# eCore_USB.net
KiCad netlist of a schematic drawn in Altium Designer
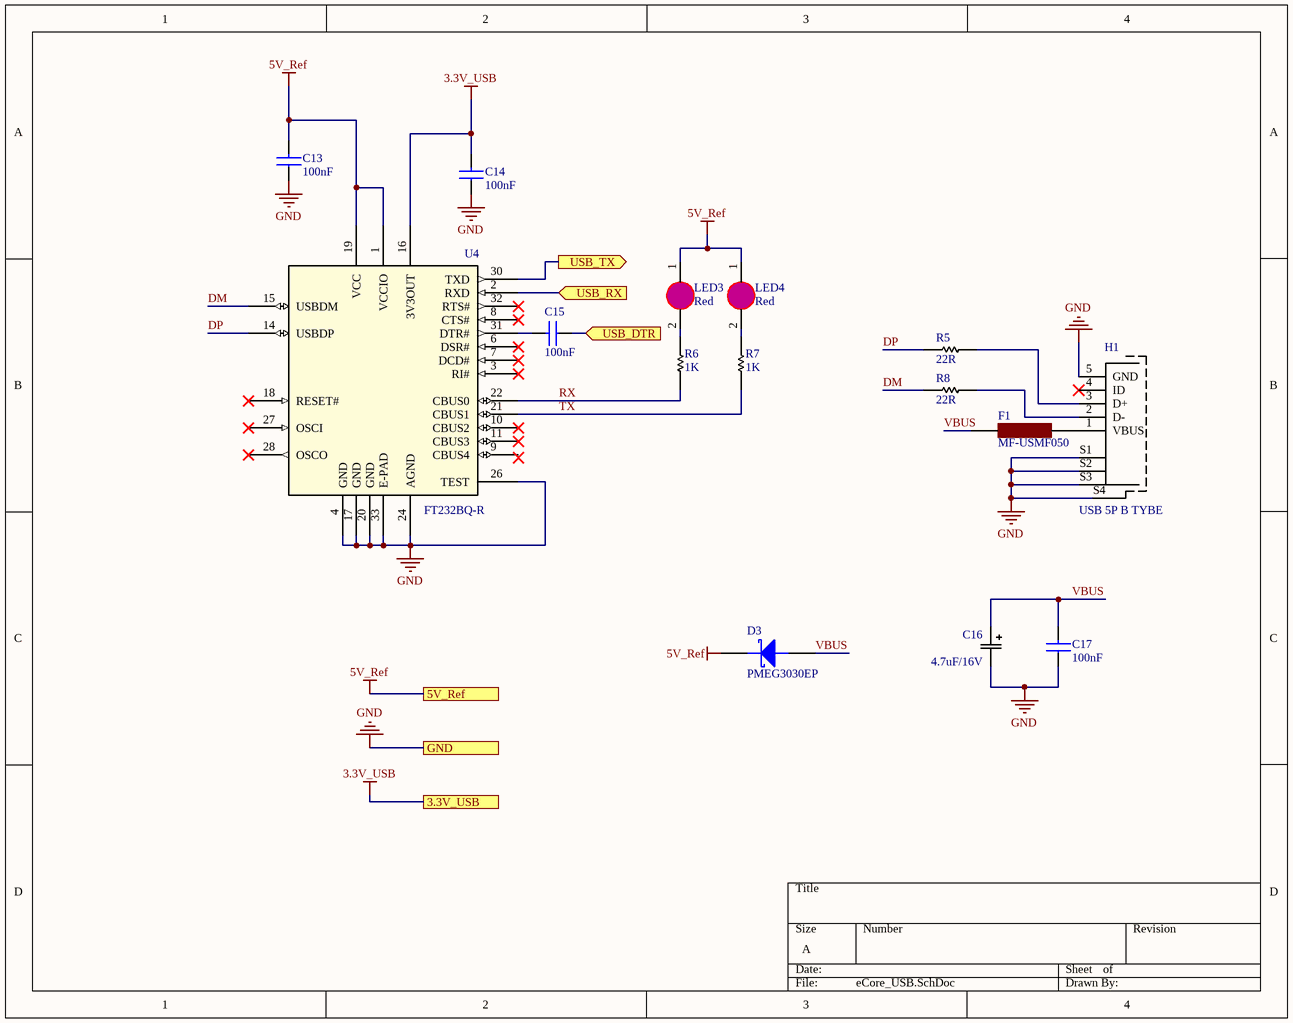
[diagram p0: eCore_USB.SchDoc]

(export (version "E")
  (design (tool "Eeschema 10.0.6"))
  (components
    (comp (ref "C13")
      (value "100nF")
      (footprint "CAPC1005X60N")
      (libsource (lib "SCHP-CAD") (part "Cap 0402"))
    )
    (comp (ref "C14")
      (value "100nF")
      (footprint "CAPC1005X60N")
      (libsource (lib "SCHP-CAD") (part "Cap 0402"))
    )
    (comp (ref "C15")
      (value "100nF")
      (footprint "CAPC1005X60N")
      (libsource (lib "SCHP-CAD") (part "Cap 0402"))
    )
    (comp (ref "C16")
      (value "4.7uF/16V")
      (footprint "CAPCP3216X180N")
      (description "Cap Tant Solid 4.7uF 16V A CASE 10% (3.2 X 1.6 X 1.6mm) SMD 3216-18 2.9 Ohm 175C Automotive T/R")
      (fields (field (name "MP") "THJA475K016RJN") (field (name "MF") "AVX"))
      (libsource (lib "SCHP-CAD") (part "CAP Tantalum Case A"))
    )
    (comp (ref "C17")
      (value "100nF")
      (footprint "CAPC1005X60N")
      (libsource (lib "SCHP-CAD") (part "Cap 0402"))
    )
    (comp (ref "D3")
      (value "PMEG3030EP")
      (footprint "SOD128")
      (libsource (lib "SCHP-CAD") (part "PMEG3030EP"))
    )
    (comp (ref "F1")
      (value "MF-USMF050")
      (footprint "Fuse MF-USMF050")
      (libsource (lib "SCHP-CAD") (part "MF-USMF050"))
    )
    (comp (ref "H1")
      (value "USB 5P B TYBE")
      (footprint "USB 5P B TYPE")
      (description "USB conector")
      (libsource (lib "SCHP-CAD") (part "USB 5P B TYBE"))
    )
    (comp (ref "LED3")
      (value "Red")
      (footprint "LEDR-0402")
      (description "LED 3mm")
      (libsource (lib "SCHP-CAD") (part "LEDSMD"))
    )
    (comp (ref "LED4")
      (value "Red")
      (footprint "LEDR-0402")
      (description "LED 3mm")
      (libsource (lib "SCHP-CAD") (part "LEDSMD"))
    )
    (comp (ref "R5")
      (value "22R")
      (footprint "RES 0402 SMD")
      (description "Resistor")
      (fields
        (field (name "MANUFACTURER") "Generic Components")
        (field (name "PUBLISHER") "Altium Hobart Technology Centre")
      )
      (libsource (lib "SCHP-CAD") (part "Res 0402"))
    )
    (comp (ref "R6")
      (value "1K")
      (footprint "RES 0402 SMD")
      (description "Resistor")
      (fields
        (field (name "MANUFACTURER") "Generic Components")
        (field (name "PUBLISHER") "Altium Hobart Technology Centre")
      )
      (libsource (lib "SCHP-CAD") (part "Res 0402"))
    )
    (comp (ref "R7")
      (value "1K")
      (footprint "RES 0402 SMD")
      (description "Resistor")
      (fields
        (field (name "MANUFACTURER") "Generic Components")
        (field (name "PUBLISHER") "Altium Hobart Technology Centre")
      )
      (libsource (lib "SCHP-CAD") (part "Res 0402"))
    )
    (comp (ref "R8")
      (value "22R")
      (footprint "RES 0402 SMD")
      (description "Resistor")
      (fields
        (field (name "MANUFACTURER") "Generic Components")
        (field (name "PUBLISHER") "Altium Hobart Technology Centre")
      )
      (libsource (lib "SCHP-CAD") (part "Res 0402"))
    )
    (comp (ref "U4")
      (value "FT232BQ-R")
      (footprint "QFN_FTDI5X5")
      (description "Imported")
      (fields (field (name "MANUFACTURER_PART_NUMBER") "FT232BQ-REEL"))
      (libsource (lib "SCHP-CAD") (part "FT232BQ-R"))
    )
  )
  (nets
    (net (code "1") (name "/DM") (class "Default")
      (node (ref "R8") (pin "1") (pinfunction "1_1") (pintype "passive"))
      (node (ref "U4") (pin "15") (pinfunction "USBDM_15") (pintype "bidirectional"))
    )
    (net (code "2") (name "/DP") (class "Default")
      (node (ref "R5") (pin "1") (pinfunction "1_1") (pintype "passive"))
      (node (ref "U4") (pin "14") (pinfunction "USBDP_14") (pintype "bidirectional"))
    )
    (net (code "3") (name "/RX") (class "Default")
      (node (ref "R6") (pin "1") (pinfunction "1_1") (pintype "passive"))
      (node (ref "U4") (pin "22") (pinfunction "CBUS0_22") (pintype "bidirectional"))
    )
    (net (code "4") (name "/TX") (class "Default")
      (node (ref "R7") (pin "1") (pinfunction "1_1") (pintype "passive"))
      (node (ref "U4") (pin "21") (pinfunction "CBUS1_21") (pintype "bidirectional"))
    )
    (net (code "5") (name "/USB_DTR") (class "Default")
      (node (ref "C15") (pin "1") (pinfunction "1_1") (pintype "passive"))
    )
    (net (code "6") (name "/USB_RX") (class "Default")
      (node (ref "U4") (pin "2") (pinfunction "RXD_2") (pintype "input"))
    )
    (net (code "7") (name "/USB_TX") (class "Default")
      (node (ref "U4") (pin "30") (pinfunction "TXD_30") (pintype "output"))
    )
    (net (code "8") (name "/VBUS") (class "Default")
      (node (ref "C16") (pin "1") (pinfunction "C1_1") (pintype "passive"))
      (node (ref "C17") (pin "2") (pinfunction "2_2") (pintype "passive"))
      (node (ref "D3") (pin "A") (pinfunction "A_A") (pintype "passive"))
      (node (ref "F1") (pin "1") (pinfunction "1_1") (pintype "passive"))
    )
    (net (code "9") (name "3.3V_USB") (class "Default")
      (node (ref "C14") (pin "2") (pinfunction "2_2") (pintype "passive"))
      (node (ref "U4") (pin "16") (pinfunction "3V3OUT_16") (pintype "power_in"))
    )
    (net (code "10") (name "5V_Ref") (class "Default")
      (node (ref "C13") (pin "2") (pinfunction "2_2") (pintype "passive"))
      (node (ref "D3") (pin "K") (pinfunction "K_K") (pintype "passive"))
      (node (ref "LED3") (pin "1") (pinfunction "A_1") (pintype "passive"))
      (node (ref "LED4") (pin "1") (pinfunction "A_1") (pintype "passive"))
      (node (ref "U4") (pin "1") (pinfunction "VCCIO_1") (pintype "power_in"))
      (node (ref "U4") (pin "19") (pinfunction "VCC_19") (pintype "power_in"))
    )
    (net (code "11") (name "GND") (class "Default")
      (node (ref "C13") (pin "1") (pinfunction "1_1") (pintype "passive"))
      (node (ref "C14") (pin "1") (pinfunction "1_1") (pintype "passive"))
      (node (ref "C16") (pin "2") (pinfunction "C2_2") (pintype "passive"))
      (node (ref "C17") (pin "1") (pinfunction "1_1") (pintype "passive"))
      (node (ref "H1") (pin "5") (pinfunction "GND_5") (pintype "passive"))
      (node (ref "H1") (pin "S1") (pinfunction "S1_S1") (pintype "passive"))
      (node (ref "H1") (pin "S2") (pinfunction "S2_S2") (pintype "passive"))
      (node (ref "H1") (pin "S3") (pinfunction "S3_S3") (pintype "passive"))
      (node (ref "H1") (pin "S4") (pinfunction "S4_S4") (pintype "passive"))
      (node (ref "U4") (pin "17") (pinfunction "GND_17") (pintype "power_in"))
      (node (ref "U4") (pin "20") (pinfunction "GND_20") (pintype "power_in"))
      (node (ref "U4") (pin "24") (pinfunction "AGND_24") (pintype "power_in"))
      (node (ref "U4") (pin "26") (pinfunction "TEST_26") (pintype "power_in"))
      (node (ref "U4") (pin "33") (pinfunction "E-PAD_33") (pintype "power_in"))
      (node (ref "U4") (pin "4") (pinfunction "GND_4") (pintype "power_in"))
    )
    (net (code "12") (name "Net-(H1-D+)") (class "Default")
      (node (ref "H1") (pin "3") (pinfunction "D+_3") (pintype "passive"))
      (node (ref "R5") (pin "2") (pinfunction "2_2") (pintype "passive"))
    )
    (net (code "13") (name "Net-(H1-D-)") (class "Default")
      (node (ref "H1") (pin "2") (pinfunction "D-_2") (pintype "passive"))
      (node (ref "R8") (pin "2") (pinfunction "2_2") (pintype "passive"))
    )
    (net (code "14") (name "Net-(H1-VBUS)") (class "Default")
      (node (ref "F1") (pin "2") (pinfunction "2_2") (pintype "passive"))
      (node (ref "H1") (pin "1") (pinfunction "VBUS_1") (pintype "passive"))
    )
    (net (code "15") (name "Net-(LED3-K)") (class "Default")
      (node (ref "LED3") (pin "2") (pinfunction "K_2") (pintype "passive"))
      (node (ref "R6") (pin "2") (pinfunction "2_2") (pintype "passive"))
    )
    (net (code "16") (name "Net-(LED4-K)") (class "Default")
      (node (ref "LED4") (pin "2") (pinfunction "K_2") (pintype "passive"))
      (node (ref "R7") (pin "2") (pinfunction "2_2") (pintype "passive"))
    )
    (net (code "17") (name "Net-(U4-DTR#)") (class "Default")
      (node (ref "C15") (pin "2") (pinfunction "2_2") (pintype "passive"))
      (node (ref "U4") (pin "31") (pinfunction "DTR#_31") (pintype "output"))
    )
    (net (code "18") (name "unconnected-(H1-ID-Pad4)") (class "Default")
      (node (ref "H1") (pin "4") (pinfunction "ID_4") (pintype "passive+no_connect"))
    )
    (net (code "19") (name "unconnected-(H1-Pad5)") (class "Default")
      (node (ref "H1") (pin "5") (pinfunction "5_5") (pintype "passive"))
    )
    (net (code "20") (name "unconnected-(H1-Pad6)") (class "Default")
      (node (ref "H1") (pin "6") (pinfunction "6_6") (pintype "passive"))
    )
    (net (code "21") (name "unconnected-(U4-CBUS2-Pad10)") (class "Default")
      (node (ref "U4") (pin "10") (pinfunction "CBUS2_10") (pintype "bidirectional+no_connect"))
    )
    (net (code "22") (name "unconnected-(U4-CBUS3-Pad11)") (class "Default")
      (node (ref "U4") (pin "11") (pinfunction "CBUS3_11") (pintype "bidirectional+no_connect"))
    )
    (net (code "23") (name "unconnected-(U4-CBUS4-Pad9)") (class "Default")
      (node (ref "U4") (pin "9") (pinfunction "CBUS4_9") (pintype "bidirectional"))
    )
    (net (code "24") (name "unconnected-(U4-CTS#-Pad8)") (class "Default")
      (node (ref "U4") (pin "8") (pinfunction "CTS#_8") (pintype "input+no_connect"))
    )
    (net (code "25") (name "unconnected-(U4-DCD#-Pad7)") (class "Default")
      (node (ref "U4") (pin "7") (pinfunction "DCD#_7") (pintype "input+no_connect"))
    )
    (net (code "26") (name "unconnected-(U4-DSR#-Pad6)") (class "Default")
      (node (ref "U4") (pin "6") (pinfunction "DSR#_6") (pintype "input+no_connect"))
    )
    (net (code "27") (name "unconnected-(U4-NC-Pad5)") (class "Default")
      (node (ref "U4") (pin "5") (pinfunction "NC_5") (pintype "passive"))
    )
    (net (code "28") (name "unconnected-(U4-NC-Pad12)") (class "Default")
      (node (ref "U4") (pin "12") (pinfunction "NC_12") (pintype "passive"))
    )
    (net (code "29") (name "unconnected-(U4-NC-Pad13)") (class "Default")
      (node (ref "U4") (pin "13") (pinfunction "NC_13") (pintype "passive"))
    )
    (net (code "30") (name "unconnected-(U4-NC-Pad23)") (class "Default")
      (node (ref "U4") (pin "23") (pinfunction "NC_23") (pintype "passive"))
    )
    (net (code "31") (name "unconnected-(U4-NC-Pad25)") (class "Default")
      (node (ref "U4") (pin "25") (pinfunction "NC_25") (pintype "passive"))
    )
    (net (code "32") (name "unconnected-(U4-NC-Pad29)") (class "Default")
      (node (ref "U4") (pin "29") (pinfunction "NC_29") (pintype "passive"))
    )
    (net (code "33") (name "unconnected-(U4-OSCI-Pad27)") (class "Default")
      (node (ref "U4") (pin "27") (pinfunction "OSCI_27") (pintype "input+no_connect"))
    )
    (net (code "34") (name "unconnected-(U4-OSCO-Pad28)") (class "Default")
      (node (ref "U4") (pin "28") (pinfunction "OSCO_28") (pintype "output+no_connect"))
    )
    (net (code "35") (name "unconnected-(U4-RESET#-Pad18)") (class "Default")
      (node (ref "U4") (pin "18") (pinfunction "RESET#_18") (pintype "input+no_connect"))
    )
    (net (code "36") (name "unconnected-(U4-RI#-Pad3)") (class "Default")
      (node (ref "U4") (pin "3") (pinfunction "RI#_3") (pintype "input+no_connect"))
    )
    (net (code "37") (name "unconnected-(U4-RTS#-Pad32)") (class "Default")
      (node (ref "U4") (pin "32") (pinfunction "RTS#_32") (pintype "output+no_connect"))
    )
  )
)
